# test5.net
KiCad netlist of a schematic drawn in EAGLE
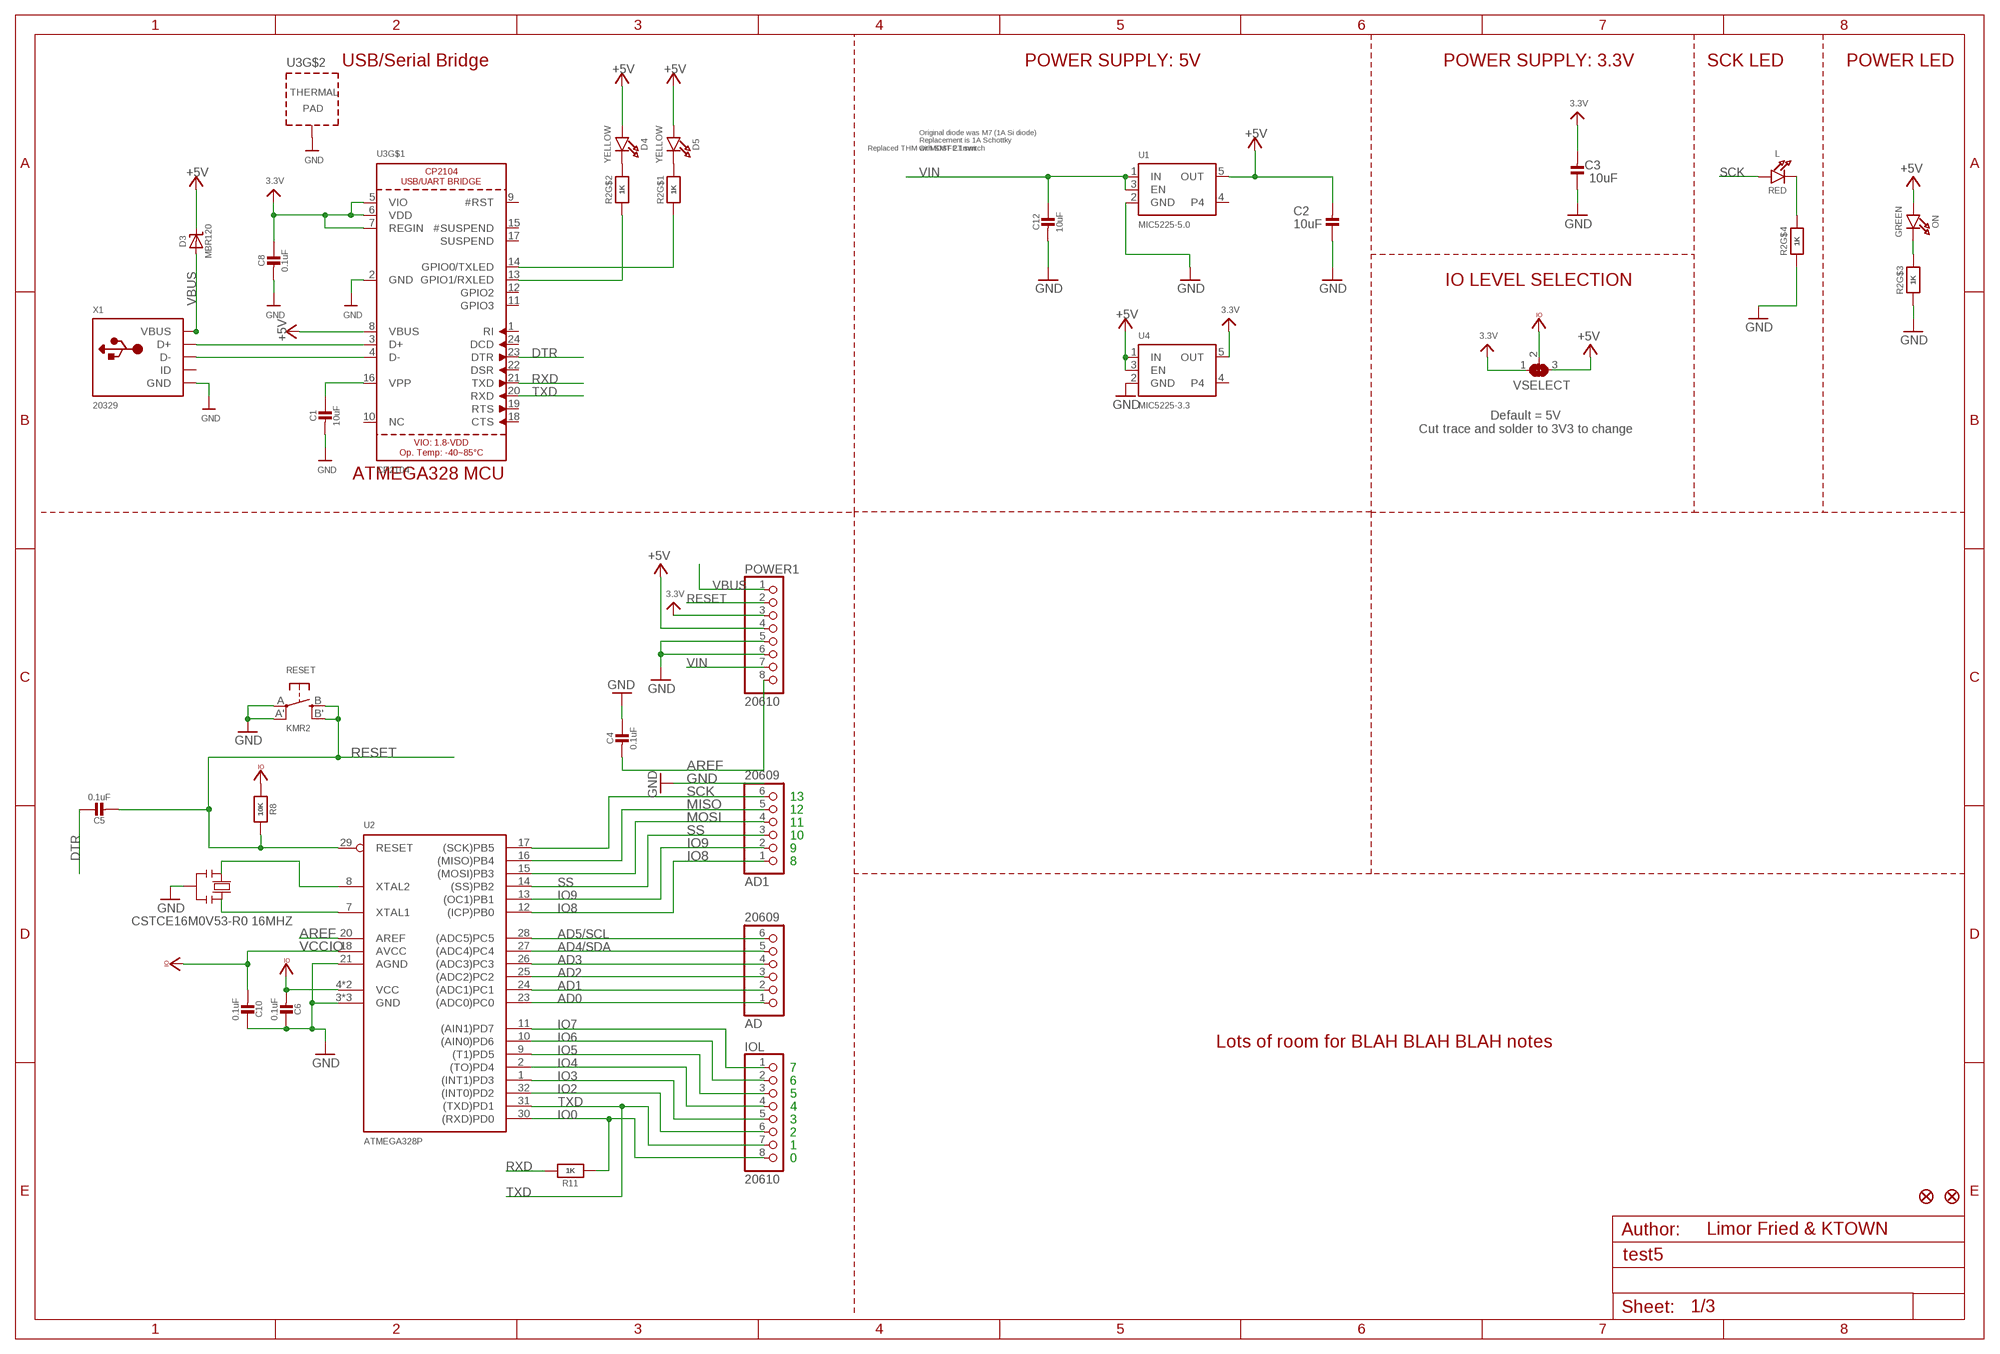
[diagram p0: schematic, sheet 1]
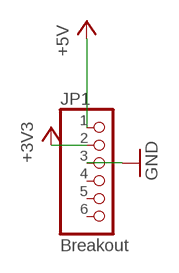
[diagram p1: schematic, sheet 2]
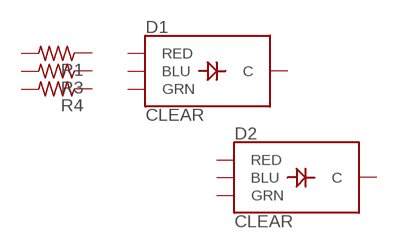
[diagram p2: schematic, sheet 3]

(export (version "E")
  (design (tool "Eeschema 10.0.6"))
  (components
    (comp (ref "D1")
      (value "CLEAR")
      (footprint "eagle-import:LED-RGB-THRU")
      (libsource (lib "eagle-import") (part "LED-RGB-CCCLEAR"))
    )
    (comp (ref "D2")
      (value "CLEAR")
      (footprint "eagle-import:LED-RGB-THRU")
      (libsource (lib "eagle-import") (part "LED-RGB-CCCLEAR"))
    )
    (comp (ref "R1")
      (value "R-US_0309/12")
      (footprint "eagle-import:0309_12")
      (libsource (lib "eagle-import") (part "R-US_0309/12"))
    )
    (comp (ref "R3")
      (value "R-US_0309/12")
      (footprint "eagle-import:0309_12")
      (libsource (lib "eagle-import") (part "R-US_0309/12"))
    )
    (comp (ref "R4")
      (value "R-US_0309/12")
      (footprint "eagle-import:0309_12")
      (libsource (lib "eagle-import") (part "R-US_0309/12"))
    )
    (comp (ref "JP1")
      (value "Breakout")
      (footprint "eagle-import:1X06_ROUND_76")
      (libsource (lib "eagle-import") (part "HEADER-1X676MIL"))
    )
    (comp (ref "AD")
      (value "20609")
      (footprint "eagle-import:1X06_ROUND")
      (libsource (lib "eagle-import") (part "HEADER-1X6ROUND"))
    )
    (comp (ref "AD1")
      (value "20609")
      (footprint "eagle-import:1X06_ROUND")
      (libsource (lib "eagle-import") (part "HEADER-1X6ROUND"))
    )
    (comp (ref "C1")
      (value "10uF")
      (footprint "eagle-import:0805-NO")
      (libsource (lib "eagle-import") (part "CAP_CERAMIC0805-NOOUTLINE"))
    )
    (comp (ref "C2")
      (value "10uF")
      (footprint "eagle-import:0805-NO")
      (libsource (lib "eagle-import") (part "CAP_CERAMIC0805-NOOUTLINE"))
    )
    (comp (ref "C3")
      (value "10uF")
      (footprint "eagle-import:0805-NO")
      (libsource (lib "eagle-import") (part "CAP_CERAMIC0805-NOOUTLINE"))
    )
    (comp (ref "C4")
      (value "0.1uF")
      (footprint "eagle-import:0805-NO")
      (libsource (lib "eagle-import") (part "CAP_CERAMIC0805-NOOUTLINE"))
    )
    (comp (ref "C5")
      (value "0.1uF")
      (footprint "eagle-import:_0805MP")
      (libsource (lib "eagle-import") (part "CAP_CERAMIC_0805MP"))
    )
    (comp (ref "C6")
      (value "0.1uF")
      (footprint "eagle-import:0805-NO")
      (libsource (lib "eagle-import") (part "CAP_CERAMIC0805-NOOUTLINE"))
    )
    (comp (ref "C8")
      (value "0.1uF")
      (footprint "eagle-import:0805-NO")
      (libsource (lib "eagle-import") (part "CAP_CERAMIC0805-NOOUTLINE"))
    )
    (comp (ref "C10")
      (value "0.1uF")
      (footprint "eagle-import:0805-NO")
      (libsource (lib "eagle-import") (part "CAP_CERAMIC0805-NOOUTLINE"))
    )
    (comp (ref "C12")
      (value "10uF")
      (footprint "eagle-import:0805-NO")
      (libsource (lib "eagle-import") (part "CAP_CERAMIC0805-NOOUTLINE"))
    )
    (comp (ref "D3")
      (value "MBR120")
      (footprint "eagle-import:SOD-123")
      (libsource (lib "eagle-import") (part "DIODE-SCHOTTKYSOD-123"))
    )
    (comp (ref "D4")
      (value "YELLOW")
      (footprint "eagle-import:CHIPLED_0805_NOOUTLINE")
      (libsource (lib "eagle-import") (part "LED0805_NOOUTLINE"))
    )
    (comp (ref "D5")
      (value "YELLOW")
      (footprint "eagle-import:CHIPLED_0805_NOOUTLINE")
      (libsource (lib "eagle-import") (part "LED0805_NOOUTLINE"))
    )
    (comp (ref "FD1")
      (value "FIDUCIAL\"\"")
      (footprint "eagle-import:FIDUCIAL_1MM")
      (libsource (lib "eagle-import") (part "FIDUCIAL{dblquote}{dblquote}"))
    )
    (comp (ref "FD2")
      (value "FIDUCIAL\"\"")
      (footprint "eagle-import:FIDUCIAL_1MM")
      (libsource (lib "eagle-import") (part "FIDUCIAL{dblquote}{dblquote}"))
    )
    (comp (ref "IOL")
      (value "20610")
      (footprint "eagle-import:1X08_ROUND")
      (libsource (lib "eagle-import") (part "HEADER-1X8ROUND"))
    )
    (comp (ref "L")
      (value "RED")
      (footprint "eagle-import:CHIPLED_0805_NOOUTLINE")
      (libsource (lib "eagle-import") (part "LED0805_NOOUTLINE"))
    )
    (comp (ref "ON")
      (value "GREEN")
      (footprint "eagle-import:CHIPLED_0805_NOOUTLINE")
      (libsource (lib "eagle-import") (part "LED0805_NOOUTLINE"))
    )
    (comp (ref "POWER1")
      (value "20610")
      (footprint "eagle-import:1X08_ROUND_70")
      (libsource (lib "eagle-import") (part "HEADER-1X870MIL"))
    )
    (comp (ref "R2")
      (value "1K")
      (footprint "eagle-import:RESPACK_4X0603")
      (libsource (lib "eagle-import") (part "RESISTOR_4PACK"))
    )
    (comp (ref "R8")
      (value "10K")
      (footprint "eagle-import:0805-NO")
      (libsource (lib "eagle-import") (part "RESISTOR0805_NOOUTLINE"))
    )
    (comp (ref "R11")
      (value "1K")
      (footprint "eagle-import:0805-NO")
      (libsource (lib "eagle-import") (part "RESISTOR0805_NOOUTLINE"))
    )
    (comp (ref "RESET")
      (value "KMR2")
      (footprint "eagle-import:BTN_KMR2_4.6X2.8")
      (libsource (lib "eagle-import") (part "SWITCH_TACT_SMT4.6X2.8"))
    )
    (comp (ref "U1")
      (value "MIC5225-5.0")
      (footprint "eagle-import:SOT23-5")
      (libsource (lib "eagle-import") (part "VREG_SOT23-5"))
    )
    (comp (ref "U2")
      (value "ATMEGA328P")
      (footprint "eagle-import:MLF32-TH")
      (libsource (lib "eagle-import") (part "ATMEGA328P"))
    )
    (comp (ref "U3")
      (value "CP2104")
      (footprint "eagle-import:QFN24_4MM_SMSC")
      (libsource (lib "eagle-import") (part "CP2104"))
    )
    (comp (ref "U4")
      (value "MIC5225-3.3")
      (footprint "eagle-import:SOT23-5")
      (libsource (lib "eagle-import") (part "VREG_SOT23-5"))
    )
    (comp (ref "VSELECT")
      (value "SOLDERJUMPER_2WAY")
      (footprint "eagle-import:SOLDERJUMPER_2WAY_OPEN_NOPASTE")
      (libsource (lib "eagle-import") (part "SOLDERJUMPER_2WAY"))
    )
    (comp (ref "X1")
      (value "20329")
      (footprint "eagle-import:4UCONN_20329_V2")
      (libsource (lib "eagle-import") (part "USB_MICRO_20329_V2"))
    )
    (comp (ref "Y2")
      (value "CSTCE16M0V53-R0 16MHZ")
      (footprint "eagle-import:RESONATOR")
      (libsource (lib "eagle-import") (part "RESONATORMU"))
    )
  )
  (nets
    (net (code "1") (name "+3V3") (class "Default")
      (node (ref "JP1") (pin "2") (pinfunction "2_2") (pintype "passive"))
    )
    (net (code "2") (name "+5V") (class "Default")
      (node (ref "C2") (pin "2") (pinfunction "2_2") (pintype "passive"))
      (node (ref "D3") (pin "C") (pinfunction "C_C") (pintype "passive"))
      (node (ref "D4") (pin "A") (pinfunction "A_A") (pintype "passive"))
      (node (ref "D5") (pin "A") (pinfunction "A_A") (pintype "passive"))
      (node (ref "JP1") (pin "1") (pinfunction "1_1") (pintype "passive"))
      (node (ref "ON") (pin "A") (pinfunction "A_A") (pintype "passive"))
      (node (ref "POWER1") (pin "4") (pinfunction "4_4") (pintype "passive"))
      (node (ref "U1") (pin "5") (pinfunction "OUT_5") (pintype "power_in"))
      (node (ref "U3") (pin "8") (pinfunction "VBUS_8") (pintype "power_in"))
      (node (ref "U4") (pin "1") (pinfunction "IN_1") (pintype "power_in"))
      (node (ref "U4") (pin "3") (pinfunction "EN_3") (pintype "input"))
      (node (ref "VSELECT") (pin "3") (pinfunction "3_3") (pintype "passive"))
    )
    (net (code "3") (name "3.3V") (class "Default")
      (node (ref "C3") (pin "2") (pinfunction "2_2") (pintype "passive"))
      (node (ref "C8") (pin "1") (pinfunction "1_1") (pintype "passive"))
      (node (ref "POWER1") (pin "3") (pinfunction "3_3") (pintype "passive"))
      (node (ref "U3") (pin "5") (pinfunction "VIO_5") (pintype "power_in"))
      (node (ref "U3") (pin "6") (pinfunction "VDD_6") (pintype "power_in"))
      (node (ref "U3") (pin "7") (pinfunction "REGIN_7") (pintype "power_in"))
      (node (ref "U4") (pin "5") (pinfunction "OUT_5") (pintype "power_in"))
      (node (ref "VSELECT") (pin "1") (pinfunction "1_1") (pintype "passive"))
    )
    (net (code "4") (name "AD0") (class "Default")
      (node (ref "AD") (pin "1") (pinfunction "1_1") (pintype "passive"))
      (node (ref "U2") (pin "23") (pinfunction "(ADC0)PC0_23") (pintype "bidirectional"))
    )
    (net (code "5") (name "AD1") (class "Default")
      (node (ref "AD") (pin "2") (pinfunction "2_2") (pintype "passive"))
      (node (ref "U2") (pin "24") (pinfunction "(ADC1)PC1_24") (pintype "bidirectional"))
    )
    (net (code "6") (name "AD2") (class "Default")
      (node (ref "AD") (pin "3") (pinfunction "3_3") (pintype "passive"))
      (node (ref "U2") (pin "25") (pinfunction "(ADC2)PC2_25") (pintype "bidirectional"))
    )
    (net (code "7") (name "AD3") (class "Default")
      (node (ref "AD") (pin "4") (pinfunction "4_4") (pintype "passive"))
      (node (ref "U2") (pin "26") (pinfunction "(ADC3)PC3_26") (pintype "bidirectional"))
    )
    (net (code "8") (name "AD4{slash}SDA") (class "Default")
      (node (ref "AD") (pin "5") (pinfunction "5_5") (pintype "passive"))
      (node (ref "U2") (pin "27") (pinfunction "(ADC4)PC4_27") (pintype "bidirectional"))
    )
    (net (code "9") (name "AD5{slash}SCL") (class "Default")
      (node (ref "AD") (pin "6") (pinfunction "6_6") (pintype "passive"))
      (node (ref "U2") (pin "28") (pinfunction "(ADC5)PC5_28") (pintype "bidirectional"))
    )
    (net (code "10") (name "AREF") (class "Default")
      (node (ref "C4") (pin "2") (pinfunction "2_2") (pintype "passive"))
      (node (ref "POWER1") (pin "8") (pinfunction "8_8") (pintype "passive"))
      (node (ref "U2") (pin "20") (pinfunction "AREF_20") (pintype "power_in"))
    )
    (net (code "11") (name "DTR") (class "Default")
      (node (ref "C5") (pin "1") (pinfunction "1_1") (pintype "passive"))
      (node (ref "U3") (pin "23") (pinfunction "DTR_23") (pintype "output"))
    )
    (net (code "12") (name "GND") (class "Default")
      (node (ref "C1") (pin "2") (pinfunction "2_2") (pintype "passive"))
      (node (ref "C10") (pin "1") (pinfunction "1_1") (pintype "passive"))
      (node (ref "C12") (pin "2") (pinfunction "2_2") (pintype "passive"))
      (node (ref "C2") (pin "1") (pinfunction "1_1") (pintype "passive"))
      (node (ref "C3") (pin "1") (pinfunction "1_1") (pintype "passive"))
      (node (ref "C4") (pin "1") (pinfunction "1_1") (pintype "passive"))
      (node (ref "C6") (pin "1") (pinfunction "1_1") (pintype "passive"))
      (node (ref "C8") (pin "2") (pinfunction "2_2") (pintype "passive"))
      (node (ref "JP1") (pin "3") (pinfunction "3_3") (pintype "passive"))
      (node (ref "POWER1") (pin "5") (pinfunction "5_5") (pintype "passive"))
      (node (ref "POWER1") (pin "6") (pinfunction "6_6") (pintype "passive"))
      (node (ref "R2") (pin "3") (pinfunction "1_3") (pintype "passive"))
      (node (ref "R2") (pin "4") (pinfunction "1_4") (pintype "passive"))
      (node (ref "RESET") (pin "A") (pinfunction "P_A") (pintype "passive"))
      (node (ref "RESET") (pin "A'") (pinfunction "P1_A'") (pintype "passive"))
      (node (ref "U1") (pin "2") (pinfunction "GND_2") (pintype "power_in"))
      (node (ref "U2") (pin "21") (pinfunction "AGND_21") (pintype "power_in"))
      (node (ref "U2") (pin "3") (pinfunction "GND_3") (pintype "power_in"))
      (node (ref "U2") (pin "5") (pinfunction "GND_5") (pintype "power_in"))
      (node (ref "U2") (pin "TH") (pinfunction "GND_TH") (pintype "power_in"))
      (node (ref "U3") (pin "2") (pinfunction "GND_2") (pintype "power_in"))
      (node (ref "U3") (pin "THERM") (pinfunction "TP_THERM") (pintype "power_in"))
      (node (ref "U4") (pin "2") (pinfunction "GND_2") (pintype "power_in"))
      (node (ref "X1") (pin "BASE@1") (pinfunction "GND_BASE@1") (pintype "power_in"))
      (node (ref "X1") (pin "BASE@2") (pinfunction "GND_BASE@2") (pintype "power_in"))
      (node (ref "X1") (pin "GND") (pinfunction "GND_GND") (pintype "power_in"))
      (node (ref "X1") (pin "SPRT@1") (pinfunction "GND_SPRT@1") (pintype "power_in"))
      (node (ref "X1") (pin "SPRT@2") (pinfunction "GND_SPRT@2") (pintype "power_in"))
      (node (ref "X1") (pin "SPRT@3") (pinfunction "GND_SPRT@3") (pintype "power_in"))
      (node (ref "X1") (pin "SPRT@4") (pinfunction "GND_SPRT@4") (pintype "power_in"))
      (node (ref "Y2") (pin "2") (pinfunction "2_2") (pintype "passive"))
    )
    (net (code "13") (name "IO0") (class "Default")
      (node (ref "IOL") (pin "8") (pinfunction "8_8") (pintype "passive"))
      (node (ref "R11") (pin "1") (pinfunction "1_1") (pintype "passive"))
      (node (ref "U2") (pin "30") (pinfunction "(RXD)PD0_30") (pintype "bidirectional"))
    )
    (net (code "14") (name "IO2") (class "Default")
      (node (ref "IOL") (pin "6") (pinfunction "6_6") (pintype "passive"))
      (node (ref "U2") (pin "32") (pinfunction "(INT0)PD2_32") (pintype "bidirectional"))
    )
    (net (code "15") (name "IO3") (class "Default")
      (node (ref "IOL") (pin "5") (pinfunction "5_5") (pintype "passive"))
      (node (ref "U2") (pin "1") (pinfunction "(INT1)PD3_1") (pintype "bidirectional"))
    )
    (net (code "16") (name "IO4") (class "Default")
      (node (ref "IOL") (pin "4") (pinfunction "4_4") (pintype "passive"))
      (node (ref "U2") (pin "2") (pinfunction "(TO)PD4_2") (pintype "bidirectional"))
    )
    (net (code "17") (name "IO5") (class "Default")
      (node (ref "IOL") (pin "3") (pinfunction "3_3") (pintype "passive"))
      (node (ref "U2") (pin "9") (pinfunction "(T1)PD5_9") (pintype "bidirectional"))
    )
    (net (code "18") (name "IO6") (class "Default")
      (node (ref "IOL") (pin "2") (pinfunction "2_2") (pintype "passive"))
      (node (ref "U2") (pin "10") (pinfunction "(AIN0)PD6_10") (pintype "bidirectional"))
    )
    (net (code "19") (name "IO7") (class "Default")
      (node (ref "IOL") (pin "1") (pinfunction "1_1") (pintype "passive"))
      (node (ref "U2") (pin "11") (pinfunction "(AIN1)PD7_11") (pintype "bidirectional"))
    )
    (net (code "20") (name "IO8") (class "Default")
      (node (ref "AD1") (pin "1") (pinfunction "1_1") (pintype "passive"))
      (node (ref "U2") (pin "12") (pinfunction "(ICP)PB0_12") (pintype "bidirectional"))
    )
    (net (code "21") (name "IO9") (class "Default")
      (node (ref "AD1") (pin "2") (pinfunction "2_2") (pintype "passive"))
      (node (ref "U2") (pin "13") (pinfunction "(OC1)PB1_13") (pintype "bidirectional"))
    )
    (net (code "22") (name "MISO") (class "Default")
      (node (ref "AD1") (pin "5") (pinfunction "5_5") (pintype "passive"))
      (node (ref "U2") (pin "16") (pinfunction "(MISO)PB4_16") (pintype "bidirectional"))
    )
    (net (code "23") (name "MOSI") (class "Default")
      (node (ref "AD1") (pin "4") (pinfunction "4_4") (pintype "passive"))
      (node (ref "U2") (pin "15") (pinfunction "(MOSI)PB3_15") (pintype "bidirectional"))
    )
    (net (code "24") (name "Net-(R2A-2)") (class "Default")
      (node (ref "D5") (pin "C") (pinfunction "C_C") (pintype "passive"))
      (node (ref "R2") (pin "8") (pinfunction "2_8") (pintype "passive"))
    )
    (net (code "25") (name "Net-(R2B-1)") (class "Default")
      (node (ref "R2") (pin "2") (pinfunction "1_2") (pintype "passive"))
      (node (ref "U3") (pin "13") (pinfunction "GPIO1/RXLED_13") (pintype "bidirectional"))
    )
    (net (code "26") (name "Net-(R2B-2)") (class "Default")
      (node (ref "D4") (pin "C") (pinfunction "C_C") (pintype "passive"))
      (node (ref "R2") (pin "7") (pinfunction "2_7") (pintype "passive"))
    )
    (net (code "27") (name "Net-(R2C-2)") (class "Default")
      (node (ref "ON") (pin "C") (pinfunction "C_C") (pintype "passive"))
      (node (ref "R2") (pin "6") (pinfunction "2_6") (pintype "passive"))
    )
    (net (code "28") (name "Net-(R2D-2)") (class "Default")
      (node (ref "L") (pin "C") (pinfunction "C_C") (pintype "passive"))
      (node (ref "R2") (pin "5") (pinfunction "2_5") (pintype "passive"))
    )
    (net (code "29") (name "Net-(U2-XTAL1)") (class "Default")
      (node (ref "U2") (pin "7") (pinfunction "XTAL1_7") (pintype "bidirectional"))
      (node (ref "Y2") (pin "3") (pinfunction "3_3") (pintype "passive"))
    )
    (net (code "30") (name "Net-(U2-XTAL2)") (class "Default")
      (node (ref "U2") (pin "8") (pinfunction "XTAL2_8") (pintype "bidirectional"))
      (node (ref "Y2") (pin "1") (pinfunction "1_1") (pintype "passive"))
    )
    (net (code "31") (name "Net-(U3A-D+)") (class "Default")
      (node (ref "U3") (pin "3") (pinfunction "D+_3") (pintype "bidirectional"))
      (node (ref "X1") (pin "D+") (pinfunction "D+_D+") (pintype "bidirectional"))
    )
    (net (code "32") (name "Net-(U3A-D-)") (class "Default")
      (node (ref "U3") (pin "4") (pinfunction "D-_4") (pintype "bidirectional"))
      (node (ref "X1") (pin "D-") (pinfunction "D-_D-") (pintype "bidirectional"))
    )
    (net (code "33") (name "Net-(U3A-GPIO0{slash}TXLED)") (class "Default")
      (node (ref "R2") (pin "1") (pinfunction "1_1") (pintype "passive"))
      (node (ref "U3") (pin "14") (pinfunction "GPIO0/TXLED_14") (pintype "bidirectional"))
    )
    (net (code "34") (name "Net-(U3A-VPP)") (class "Default")
      (node (ref "C1") (pin "1") (pinfunction "1_1") (pintype "passive"))
      (node (ref "U3") (pin "16") (pinfunction "VPP_16") (pintype "bidirectional"))
    )
    (net (code "35") (name "RESET") (class "Default")
      (node (ref "C5") (pin "2") (pinfunction "2_2") (pintype "passive"))
      (node (ref "POWER1") (pin "2") (pinfunction "2_2") (pintype "passive"))
      (node (ref "R8") (pin "1") (pinfunction "1_1") (pintype "passive"))
      (node (ref "RESET") (pin "B") (pinfunction "S_B") (pintype "passive"))
      (node (ref "RESET") (pin "B'") (pinfunction "S1_B'") (pintype "passive"))
      (node (ref "U2") (pin "29") (pinfunction "RESET_29") (pintype "bidirectional"))
    )
    (net (code "36") (name "RXD") (class "Default")
      (node (ref "R11") (pin "2") (pinfunction "2_2") (pintype "passive"))
      (node (ref "U3") (pin "21") (pinfunction "TXD_21") (pintype "output"))
    )
    (net (code "37") (name "SCK") (class "Default")
      (node (ref "AD1") (pin "6") (pinfunction "6_6") (pintype "passive"))
      (node (ref "L") (pin "A") (pinfunction "A_A") (pintype "passive"))
      (node (ref "U2") (pin "17") (pinfunction "(SCK)PB5_17") (pintype "bidirectional"))
    )
    (net (code "38") (name "SS") (class "Default")
      (node (ref "AD1") (pin "3") (pinfunction "3_3") (pintype "passive"))
      (node (ref "U2") (pin "14") (pinfunction "(SS)PB2_14") (pintype "bidirectional"))
    )
    (net (code "39") (name "TXD") (class "Default")
      (node (ref "IOL") (pin "7") (pinfunction "7_7") (pintype "passive"))
      (node (ref "U2") (pin "31") (pinfunction "(TXD)PD1_31") (pintype "bidirectional"))
      (node (ref "U3") (pin "20") (pinfunction "RXD_20") (pintype "input"))
    )
    (net (code "40") (name "VBUS") (class "Default")
      (node (ref "D3") (pin "A") (pinfunction "A_A") (pintype "passive"))
      (node (ref "POWER1") (pin "1") (pinfunction "1_1") (pintype "passive"))
      (node (ref "X1") (pin "VBUS") (pinfunction "VBUS_VBUS") (pintype "power_in"))
    )
    (net (code "41") (name "VCCIO") (class "Default")
      (node (ref "C10") (pin "2") (pinfunction "2_2") (pintype "passive"))
      (node (ref "C6") (pin "2") (pinfunction "2_2") (pintype "passive"))
      (node (ref "R8") (pin "2") (pinfunction "2_2") (pintype "passive"))
      (node (ref "U2") (pin "18") (pinfunction "AVCC_18") (pintype "power_in"))
      (node (ref "U2") (pin "4") (pinfunction "VCC_4") (pintype "power_in"))
      (node (ref "U2") (pin "6") (pinfunction "VCC_6") (pintype "power_in"))
      (node (ref "VSELECT") (pin "2") (pinfunction "2_2") (pintype "passive"))
    )
    (net (code "42") (name "VIN") (class "Default")
      (node (ref "C12") (pin "1") (pinfunction "1_1") (pintype "passive"))
      (node (ref "POWER1") (pin "7") (pinfunction "7_7") (pintype "passive"))
      (node (ref "U1") (pin "1") (pinfunction "IN_1") (pintype "power_in"))
      (node (ref "U1") (pin "3") (pinfunction "EN_3") (pintype "input"))
    )
    (net (code "43") (name "unconnected-(D1-BLU-Pad4)") (class "Default")
      (node (ref "D1") (pin "4") (pinfunction "BLU_4") (pintype "bidirectional"))
    )
    (net (code "44") (name "unconnected-(D1-C-Pad2)") (class "Default")
      (node (ref "D1") (pin "2") (pinfunction "C_2") (pintype "bidirectional"))
    )
    (net (code "45") (name "unconnected-(D1-GRN-Pad3)") (class "Default")
      (node (ref "D1") (pin "3") (pinfunction "GRN_3") (pintype "bidirectional"))
    )
    (net (code "46") (name "unconnected-(D1-RED-Pad1)") (class "Default")
      (node (ref "D1") (pin "1") (pinfunction "RED_1") (pintype "bidirectional"))
    )
    (net (code "47") (name "unconnected-(D2-BLU-Pad4)") (class "Default")
      (node (ref "D2") (pin "4") (pinfunction "BLU_4") (pintype "bidirectional"))
    )
    (net (code "48") (name "unconnected-(D2-C-Pad2)") (class "Default")
      (node (ref "D2") (pin "2") (pinfunction "C_2") (pintype "bidirectional"))
    )
    (net (code "49") (name "unconnected-(D2-GRN-Pad3)") (class "Default")
      (node (ref "D2") (pin "3") (pinfunction "GRN_3") (pintype "bidirectional"))
    )
    (net (code "50") (name "unconnected-(D2-RED-Pad1)") (class "Default")
      (node (ref "D2") (pin "1") (pinfunction "RED_1") (pintype "bidirectional"))
    )
    (net (code "51") (name "unconnected-(JP1-Pad4)") (class "Default")
      (node (ref "JP1") (pin "4") (pinfunction "4_4") (pintype "passive"))
    )
    (net (code "52") (name "unconnected-(JP1-Pad5)") (class "Default")
      (node (ref "JP1") (pin "5") (pinfunction "5_5") (pintype "passive"))
    )
    (net (code "53") (name "unconnected-(JP1-Pad6)") (class "Default")
      (node (ref "JP1") (pin "6") (pinfunction "6_6") (pintype "passive"))
    )
    (net (code "54") (name "unconnected-(R1-Pad1)") (class "Default")
      (node (ref "R1") (pin "1") (pinfunction "1_1") (pintype "passive"))
    )
    (net (code "55") (name "unconnected-(R1-Pad2)") (class "Default")
      (node (ref "R1") (pin "2") (pinfunction "2_2") (pintype "passive"))
    )
    (net (code "56") (name "unconnected-(R3-Pad1)") (class "Default")
      (node (ref "R3") (pin "1") (pinfunction "1_1") (pintype "passive"))
    )
    (net (code "57") (name "unconnected-(R3-Pad2)") (class "Default")
      (node (ref "R3") (pin "2") (pinfunction "2_2") (pintype "passive"))
    )
    (net (code "58") (name "unconnected-(R4-Pad1)") (class "Default")
      (node (ref "R4") (pin "1") (pinfunction "1_1") (pintype "passive"))
    )
    (net (code "59") (name "unconnected-(R4-Pad2)") (class "Default")
      (node (ref "R4") (pin "2") (pinfunction "2_2") (pintype "passive"))
    )
    (net (code "60") (name "unconnected-(U1-P4-Pad4)") (class "Default")
      (node (ref "U1") (pin "4") (pinfunction "P4_4") (pintype "bidirectional"))
    )
    (net (code "61") (name "unconnected-(U3A-#RST-Pad9)") (class "Default")
      (node (ref "U3") (pin "9") (pinfunction "#RST_9") (pintype "bidirectional"))
    )
    (net (code "62") (name "unconnected-(U3A-#SUSPEND-Pad15)") (class "Default")
      (node (ref "U3") (pin "15") (pinfunction "#SUSPEND_15") (pintype "output"))
    )
    (net (code "63") (name "unconnected-(U3A-CTS-Pad18)") (class "Default")
      (node (ref "U3") (pin "18") (pinfunction "CTS_18") (pintype "input"))
    )
    (net (code "64") (name "unconnected-(U3A-DCD-Pad24)") (class "Default")
      (node (ref "U3") (pin "24") (pinfunction "DCD_24") (pintype "input"))
    )
    (net (code "65") (name "unconnected-(U3A-DSR-Pad22)") (class "Default")
      (node (ref "U3") (pin "22") (pinfunction "DSR_22") (pintype "input"))
    )
    (net (code "66") (name "unconnected-(U3A-GPIO2-Pad12)") (class "Default")
      (node (ref "U3") (pin "12") (pinfunction "GPIO2_12") (pintype "bidirectional"))
    )
    (net (code "67") (name "unconnected-(U3A-GPIO3-Pad11)") (class "Default")
      (node (ref "U3") (pin "11") (pinfunction "GPIO3_11") (pintype "bidirectional"))
    )
    (net (code "68") (name "unconnected-(U3A-NC-Pad10)") (class "Default")
      (node (ref "U3") (pin "10") (pinfunction "NC_10") (pintype "no_connect"))
    )
    (net (code "69") (name "unconnected-(U3A-RI-Pad1)") (class "Default")
      (node (ref "U3") (pin "1") (pinfunction "RI_1") (pintype "input"))
    )
    (net (code "70") (name "unconnected-(U3A-RTS-Pad19)") (class "Default")
      (node (ref "U3") (pin "19") (pinfunction "RTS_19") (pintype "output"))
    )
    (net (code "71") (name "unconnected-(U3A-SUSPEND-Pad17)") (class "Default")
      (node (ref "U3") (pin "17") (pinfunction "SUSPEND_17") (pintype "output"))
    )
    (net (code "72") (name "unconnected-(U4-P4-Pad4)") (class "Default")
      (node (ref "U4") (pin "4") (pinfunction "P4_4") (pintype "bidirectional"))
    )
    (net (code "73") (name "unconnected-(X1-PadID)") (class "Default")
      (node (ref "X1") (pin "ID") (pinfunction "ID_ID") (pintype "bidirectional"))
    )
  )
)
